# Moisture_senosor.net
KiCad netlist of a schematic drawn in EAGLE
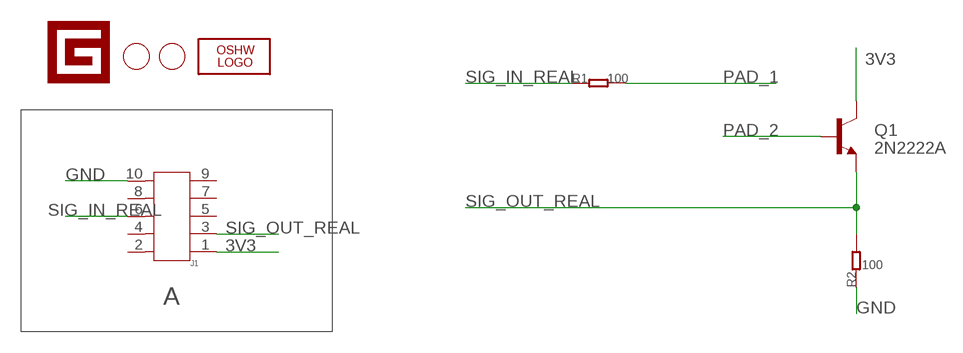
[diagram p0: schematic, sheet 1]

(export (version "E")
  (design (tool "Eeschema 10.0.6"))
  (components
    (comp (ref "J1")
      (value "HEADER-SHF-105-01-L-D-SM")
      (footprint "eagle-import:SHF-105-01-L-D-SM")
      (libsource (lib "eagle-import") (part "HEADER-SHF-105-01-L-D-SM"))
    )
    (comp (ref "LOGO1")
      (value "LOGO-OSHW-FILLX0150-NT")
      (footprint "eagle-import:OSHW_FILLX150_NOTEXT")
      (libsource (lib "eagle-import") (part "LOGO-OSHW-FILLX0150-NT"))
    )
    (comp (ref "Q1")
      (value "2N2222A")
      (footprint "eagle-import:TO-92")
      (libsource (lib "eagle-import") (part "TRANSISTOR_NPNTO92"))
    )
    (comp (ref "R1")
      (value "100")
      (footprint "eagle-import:0603")
      (libsource (lib "eagle-import") (part "R-0603"))
    )
    (comp (ref "R2")
      (value "100")
      (footprint "eagle-import:0603")
      (libsource (lib "eagle-import") (part "R-0603"))
    )
    (comp (ref "U$1")
      (value "LOGO-GADGETEER-NORMAL")
      (footprint "eagle-import:GADGETEER-SILK")
      (libsource (lib "eagle-import") (part "LOGO-GADGETEER-NORMAL"))
    )
    (comp (ref "U$2")
      (value "PAD-HOLE'3.2/7.0'")
      (footprint "eagle-import:HOLE-D-3.2_7.0")
      (libsource (lib "eagle-import") (part "PAD-HOLE'3.2/7.0'"))
    )
    (comp (ref "U$3")
      (value "PAD-HOLE'3.2/7.0'")
      (footprint "eagle-import:HOLE-D-3.2_7.0")
      (libsource (lib "eagle-import") (part "PAD-HOLE'3.2/7.0'"))
    )
  )
  (nets
    (net (code "1") (name "/3V3") (class "Default")
      (node (ref "J1") (pin "1") (pinfunction "P$1_1") (pintype "bidirectional"))
      (node (ref "Q1") (pin "3") (pinfunction "C_3") (pintype "passive"))
    )
    (net (code "2") (name "/GND") (class "Default")
      (node (ref "J1") (pin "10") (pinfunction "P$10_10") (pintype "bidirectional"))
      (node (ref "R2") (pin "1") (pinfunction "1_1") (pintype "passive"))
    )
    (net (code "3") (name "/PAD_1") (class "Default")
      (node (ref "R1") (pin "2") (pinfunction "2_2") (pintype "passive"))
    )
    (net (code "4") (name "/PAD_2") (class "Default")
      (node (ref "Q1") (pin "2") (pinfunction "B_2") (pintype "passive"))
    )
    (net (code "5") (name "/SIG_IN_REAL") (class "Default")
      (node (ref "J1") (pin "6") (pinfunction "P$6_6") (pintype "bidirectional"))
      (node (ref "R1") (pin "1") (pinfunction "1_1") (pintype "passive"))
    )
    (net (code "6") (name "/SIG_OUT_REAL") (class "Default")
      (node (ref "J1") (pin "3") (pinfunction "P$3_3") (pintype "bidirectional"))
      (node (ref "Q1") (pin "1") (pinfunction "E_1") (pintype "passive"))
      (node (ref "R2") (pin "2") (pinfunction "2_2") (pintype "passive"))
    )
    (net (code "7") (name "unconnected-(J1-P$2-Pad2)") (class "Default")
      (node (ref "J1") (pin "2") (pinfunction "P$2_2") (pintype "bidirectional"))
    )
    (net (code "8") (name "unconnected-(J1-P$4-Pad4)") (class "Default")
      (node (ref "J1") (pin "4") (pinfunction "P$4_4") (pintype "bidirectional"))
    )
    (net (code "9") (name "unconnected-(J1-P$5-Pad5)") (class "Default")
      (node (ref "J1") (pin "5") (pinfunction "P$5_5") (pintype "bidirectional"))
    )
    (net (code "10") (name "unconnected-(J1-P$7-Pad7)") (class "Default")
      (node (ref "J1") (pin "7") (pinfunction "P$7_7") (pintype "bidirectional"))
    )
    (net (code "11") (name "unconnected-(J1-P$8-Pad8)") (class "Default")
      (node (ref "J1") (pin "8") (pinfunction "P$8_8") (pintype "bidirectional"))
    )
    (net (code "12") (name "unconnected-(J1-P$9-Pad9)") (class "Default")
      (node (ref "J1") (pin "9") (pinfunction "P$9_9") (pintype "bidirectional"))
    )
  )
)
